# sensorboard_spectrometer_rev0.net
KiCad netlist of a schematic drawn in EAGLE
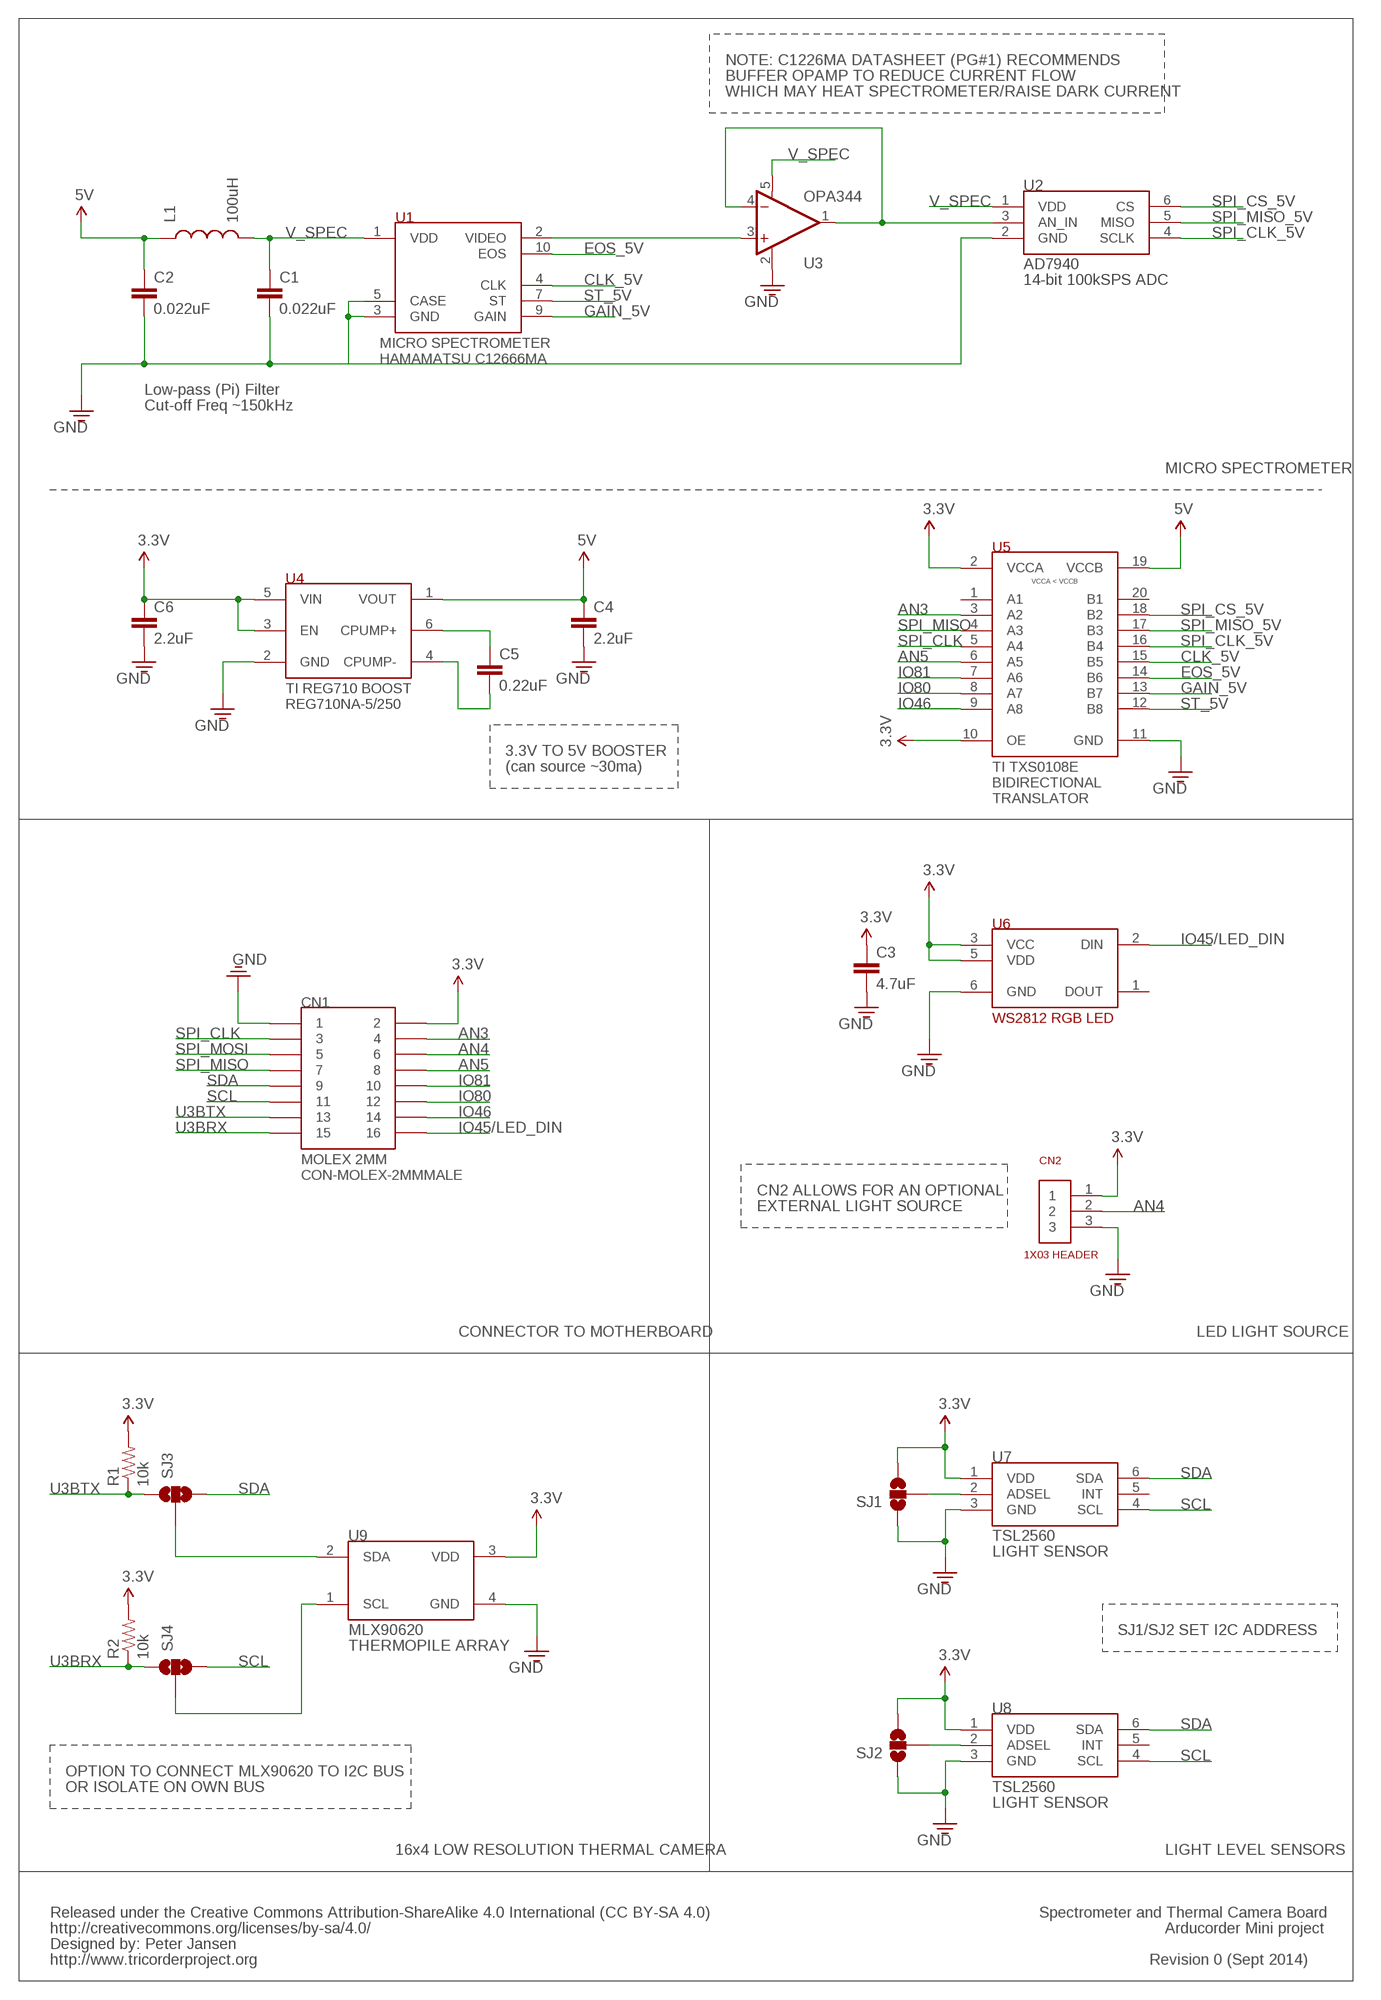
[diagram p0: schematic, sheet 1]

(export (version "E")
  (design (tool "Eeschema 10.0.6"))
  (components
    (comp (ref "C1")
      (value "0.022uF")
      (footprint "eagle-import:0603")
      (libsource (lib "eagle-import") (part "notes_mark5_CAP0603"))
    )
    (comp (ref "C2")
      (value "0.022uF")
      (footprint "eagle-import:0603")
      (libsource (lib "eagle-import") (part "notes_mark5_CAP0603"))
    )
    (comp (ref "C3")
      (value "4.7uF")
      (footprint "eagle-import:0603")
      (libsource (lib "eagle-import") (part "notes_mark5a_CAP0603"))
    )
    (comp (ref "C4")
      (value "2.2uF")
      (footprint "eagle-import:0603")
      (libsource (lib "eagle-import") (part "CAP0603"))
    )
    (comp (ref "C5")
      (value "0.22uF")
      (footprint "eagle-import:0603")
      (libsource (lib "eagle-import") (part "CAP0603"))
    )
    (comp (ref "C6")
      (value "2.2uF")
      (footprint "eagle-import:0603")
      (libsource (lib "eagle-import") (part "CAP0603"))
    )
    (comp (ref "CN1")
      (value "CON-MOLEX-2MMMALE")
      (footprint "eagle-import:MOLEX-0877591650")
      (libsource (lib "eagle-import") (part "CON-MOLEX-2MMMALE"))
    )
    (comp (ref "CN2")
      (value "1X03")
      (footprint "eagle-import:1X03")
      (libsource (lib "eagle-import") (part "1X03"))
    )
    (comp (ref "L1")
      (value "100uH")
      (footprint "eagle-import:0805")
      (libsource (lib "eagle-import") (part "INDUCTOR0805"))
    )
    (comp (ref "R1")
      (value "10k")
      (footprint "eagle-import:0603")
      (libsource (lib "eagle-import") (part "RESISTOR0603"))
    )
    (comp (ref "R2")
      (value "10k")
      (footprint "eagle-import:0603")
      (libsource (lib "eagle-import") (part "RESISTOR0603"))
    )
    (comp (ref "SJ1")
      (value "SOLDERJUMPER_2WAYPASTE1&2")
      (footprint "eagle-import:SJ_3_PASTE1&2")
      (libsource (lib "eagle-import") (part "SOLDERJUMPER_2WAYPASTE1&2"))
    )
    (comp (ref "SJ2")
      (value "SOLDERJUMPER_2WAYPASTE2&3")
      (footprint "eagle-import:SJ_3_PASTE2&3")
      (libsource (lib "eagle-import") (part "SOLDERJUMPER_2WAYPASTE2&3"))
    )
    (comp (ref "SJ3")
      (value "SOLDERJUMPER_2WAYPASTE1&2")
      (footprint "eagle-import:SJ_3_PASTE1&2")
      (libsource (lib "eagle-import") (part "SOLDERJUMPER_2WAYPASTE1&2"))
    )
    (comp (ref "SJ4")
      (value "SOLDERJUMPER_2WAYPASTE1&2")
      (footprint "eagle-import:SJ_3_PASTE1&2")
      (libsource (lib "eagle-import") (part "SOLDERJUMPER_2WAYPASTE1&2"))
    )
    (comp (ref "U1")
      (value "MICROSPEC-C12666MA")
      (footprint "eagle-import:C12666MA")
      (libsource (lib "eagle-import") (part "MICROSPEC-C12666MA"))
    )
    (comp (ref "U2")
      (value "AD7940")
      (footprint "eagle-import:SOT-23-6L")
      (libsource (lib "eagle-import") (part "AD7940"))
    )
    (comp (ref "U3")
      (value "OPA344")
      (footprint "eagle-import:SOT23-5")
      (libsource (lib "eagle-import") (part "OPA344"))
    )
    (comp (ref "U4")
      (value "REG710NA-5/250")
      (footprint "eagle-import:SOT-23-6L")
      (libsource (lib "eagle-import") (part "TI-REG710"))
    )
    (comp (ref "U5")
      (value "TRANSLATOR-TXS0108E")
      (footprint "eagle-import:TSSOP-20")
      (libsource (lib "eagle-import") (part "TRANSLATOR-TXS0108E"))
    )
    (comp (ref "U6")
      (value "WS2812_NEOPIXEL")
      (footprint "eagle-import:WS2812")
      (libsource (lib "eagle-import") (part "WS2812_NEOPIXEL"))
    )
    (comp (ref "U7")
      (value "TSL2561")
      (footprint "eagle-import:TMB-6")
      (libsource (lib "eagle-import") (part "TSL2561"))
    )
    (comp (ref "U8")
      (value "TSL2561")
      (footprint "eagle-import:TMB-6")
      (libsource (lib "eagle-import") (part "TSL2561"))
    )
    (comp (ref "U9")
      (value "MLX90620")
      (footprint "eagle-import:MLX90620")
      (libsource (lib "eagle-import") (part "MLX90620"))
    )
  )
  (nets
    (net (code "1") (name "/AN3") (class "Default")
      (node (ref "CN1") (pin "4") (pinfunction "4_4") (pintype "bidirectional"))
      (node (ref "U5") (pin "3") (pinfunction "A2_3") (pintype "bidirectional"))
    )
    (net (code "2") (name "/AN4") (class "Default")
      (node (ref "CN1") (pin "6") (pinfunction "6_6") (pintype "bidirectional"))
      (node (ref "CN2") (pin "2") (pinfunction "2_2") (pintype "bidirectional"))
    )
    (net (code "3") (name "/AN5") (class "Default")
      (node (ref "CN1") (pin "8") (pinfunction "8_8") (pintype "bidirectional"))
      (node (ref "U5") (pin "6") (pinfunction "A5_6") (pintype "bidirectional"))
    )
    (net (code "4") (name "/CLK_5V") (class "Default")
      (node (ref "U1") (pin "4") (pinfunction "CLK_4") (pintype "bidirectional"))
      (node (ref "U5") (pin "15") (pinfunction "B5_15") (pintype "bidirectional"))
    )
    (net (code "5") (name "/EOS_5V") (class "Default")
      (node (ref "U1") (pin "10") (pinfunction "EOS_10") (pintype "bidirectional"))
      (node (ref "U5") (pin "14") (pinfunction "B6_14") (pintype "bidirectional"))
    )
    (net (code "6") (name "/GAIN_5V") (class "Default")
      (node (ref "U1") (pin "9") (pinfunction "GAIN_9") (pintype "bidirectional"))
      (node (ref "U5") (pin "13") (pinfunction "B7_13") (pintype "bidirectional"))
    )
    (net (code "7") (name "/IO45{slash}LED_DIN") (class "Default")
      (node (ref "CN1") (pin "16") (pinfunction "16_16") (pintype "bidirectional"))
      (node (ref "U6") (pin "2") (pinfunction "DIN_2") (pintype "bidirectional"))
    )
    (net (code "8") (name "/IO46") (class "Default")
      (node (ref "CN1") (pin "14") (pinfunction "14_14") (pintype "bidirectional"))
      (node (ref "U5") (pin "9") (pinfunction "A8_9") (pintype "bidirectional"))
    )
    (net (code "9") (name "/IO80") (class "Default")
      (node (ref "CN1") (pin "12") (pinfunction "12_12") (pintype "bidirectional"))
      (node (ref "U5") (pin "8") (pinfunction "A7_8") (pintype "bidirectional"))
    )
    (net (code "10") (name "/IO81") (class "Default")
      (node (ref "CN1") (pin "10") (pinfunction "10_10") (pintype "bidirectional"))
      (node (ref "U5") (pin "7") (pinfunction "A6_7") (pintype "bidirectional"))
    )
    (net (code "11") (name "/SCL") (class "Default")
      (node (ref "CN1") (pin "11") (pinfunction "11_11") (pintype "bidirectional"))
      (node (ref "SJ4") (pin "3") (pinfunction "3_3") (pintype "passive"))
      (node (ref "U7") (pin "4") (pinfunction "SCL_4") (pintype "bidirectional"))
      (node (ref "U8") (pin "4") (pinfunction "SCL_4") (pintype "bidirectional"))
    )
    (net (code "12") (name "/SDA") (class "Default")
      (node (ref "CN1") (pin "9") (pinfunction "9_9") (pintype "bidirectional"))
      (node (ref "SJ3") (pin "3") (pinfunction "3_3") (pintype "passive"))
      (node (ref "U7") (pin "6") (pinfunction "SDA_6") (pintype "bidirectional"))
      (node (ref "U8") (pin "6") (pinfunction "SDA_6") (pintype "bidirectional"))
    )
    (net (code "13") (name "/SPI_CLK") (class "Default")
      (node (ref "CN1") (pin "3") (pinfunction "3_3") (pintype "bidirectional"))
      (node (ref "U5") (pin "5") (pinfunction "A4_5") (pintype "bidirectional"))
    )
    (net (code "14") (name "/SPI_CLK_5V") (class "Default")
      (node (ref "U2") (pin "4") (pinfunction "SCLK_4") (pintype "bidirectional"))
      (node (ref "U5") (pin "16") (pinfunction "B4_16") (pintype "bidirectional"))
    )
    (net (code "15") (name "/SPI_CS_5V") (class "Default")
      (node (ref "U2") (pin "6") (pinfunction "CS_6") (pintype "bidirectional"))
      (node (ref "U5") (pin "18") (pinfunction "B2_18") (pintype "bidirectional"))
    )
    (net (code "16") (name "/SPI_MISO") (class "Default")
      (node (ref "CN1") (pin "7") (pinfunction "7_7") (pintype "bidirectional"))
      (node (ref "U5") (pin "4") (pinfunction "A3_4") (pintype "bidirectional"))
    )
    (net (code "17") (name "/SPI_MISO_5V") (class "Default")
      (node (ref "U2") (pin "5") (pinfunction "MISO_5") (pintype "bidirectional"))
      (node (ref "U5") (pin "17") (pinfunction "B3_17") (pintype "bidirectional"))
    )
    (net (code "18") (name "/SPI_MOSI") (class "Default")
      (node (ref "CN1") (pin "5") (pinfunction "5_5") (pintype "bidirectional"))
    )
    (net (code "19") (name "/ST_5V") (class "Default")
      (node (ref "U1") (pin "7") (pinfunction "ST_7") (pintype "bidirectional"))
      (node (ref "U5") (pin "12") (pinfunction "B8_12") (pintype "bidirectional"))
    )
    (net (code "20") (name "/U3BRX") (class "Default")
      (node (ref "CN1") (pin "15") (pinfunction "15_15") (pintype "bidirectional"))
      (node (ref "R2") (pin "1") (pinfunction "1_1") (pintype "passive"))
      (node (ref "SJ4") (pin "1") (pinfunction "1_1") (pintype "passive"))
    )
    (net (code "21") (name "/U3BTX") (class "Default")
      (node (ref "CN1") (pin "13") (pinfunction "13_13") (pintype "bidirectional"))
      (node (ref "R1") (pin "1") (pinfunction "1_1") (pintype "passive"))
      (node (ref "SJ3") (pin "1") (pinfunction "1_1") (pintype "passive"))
    )
    (net (code "22") (name "/V_SPEC") (class "Default")
      (node (ref "C1") (pin "1") (pinfunction "1_1") (pintype "passive"))
      (node (ref "L1") (pin "2") (pinfunction "2_2") (pintype "passive"))
      (node (ref "U1") (pin "1") (pinfunction "VDD_1") (pintype "bidirectional"))
      (node (ref "U2") (pin "1") (pinfunction "VDD_1") (pintype "bidirectional"))
      (node (ref "U3") (pin "5") (pinfunction "V+_5") (pintype "power_in"))
    )
    (net (code "23") (name "3.3V") (class "Default")
      (node (ref "C3") (pin "1") (pinfunction "1_1") (pintype "passive"))
      (node (ref "C6") (pin "1") (pinfunction "1_1") (pintype "passive"))
      (node (ref "CN1") (pin "2") (pinfunction "2_2") (pintype "bidirectional"))
      (node (ref "CN2") (pin "1") (pinfunction "1_1") (pintype "bidirectional"))
      (node (ref "R1") (pin "2") (pinfunction "2_2") (pintype "passive"))
      (node (ref "R2") (pin "2") (pinfunction "2_2") (pintype "passive"))
      (node (ref "SJ1") (pin "3") (pinfunction "3_3") (pintype "passive"))
      (node (ref "SJ2") (pin "3") (pinfunction "3_3") (pintype "passive"))
      (node (ref "U4") (pin "3") (pinfunction "EN_3") (pintype "bidirectional"))
      (node (ref "U4") (pin "5") (pinfunction "VIN_5") (pintype "bidirectional"))
      (node (ref "U5") (pin "10") (pinfunction "OE_10") (pintype "bidirectional"))
      (node (ref "U5") (pin "2") (pinfunction "VCCA_2") (pintype "bidirectional"))
      (node (ref "U6") (pin "3") (pinfunction "VCC_3") (pintype "bidirectional"))
      (node (ref "U6") (pin "5") (pinfunction "VDD_5") (pintype "bidirectional"))
      (node (ref "U7") (pin "1") (pinfunction "VDD_1") (pintype "bidirectional"))
      (node (ref "U8") (pin "1") (pinfunction "VDD_1") (pintype "bidirectional"))
      (node (ref "U9") (pin "3") (pinfunction "VDD_3") (pintype "bidirectional"))
    )
    (net (code "24") (name "5V") (class "Default")
      (node (ref "C2") (pin "1") (pinfunction "1_1") (pintype "passive"))
      (node (ref "C4") (pin "1") (pinfunction "1_1") (pintype "passive"))
      (node (ref "L1") (pin "1") (pinfunction "1_1") (pintype "passive"))
      (node (ref "U4") (pin "1") (pinfunction "VOUT_1") (pintype "bidirectional"))
      (node (ref "U5") (pin "19") (pinfunction "VCCB_19") (pintype "bidirectional"))
    )
    (net (code "25") (name "GND") (class "Default")
      (node (ref "C1") (pin "2") (pinfunction "2_2") (pintype "passive"))
      (node (ref "C2") (pin "2") (pinfunction "2_2") (pintype "passive"))
      (node (ref "C3") (pin "2") (pinfunction "2_2") (pintype "passive"))
      (node (ref "C4") (pin "2") (pinfunction "2_2") (pintype "passive"))
      (node (ref "C6") (pin "2") (pinfunction "2_2") (pintype "passive"))
      (node (ref "CN1") (pin "1") (pinfunction "1_1") (pintype "bidirectional"))
      (node (ref "CN2") (pin "3") (pinfunction "3_3") (pintype "bidirectional"))
      (node (ref "SJ1") (pin "1") (pinfunction "1_1") (pintype "passive"))
      (node (ref "SJ2") (pin "1") (pinfunction "1_1") (pintype "passive"))
      (node (ref "U1") (pin "3") (pinfunction "GND_3") (pintype "bidirectional"))
      (node (ref "U1") (pin "5") (pinfunction "CASE_5") (pintype "bidirectional"))
      (node (ref "U2") (pin "2") (pinfunction "GND_2") (pintype "bidirectional"))
      (node (ref "U3") (pin "2") (pinfunction "V-_2") (pintype "power_in"))
      (node (ref "U4") (pin "2") (pinfunction "GND_2") (pintype "bidirectional"))
      (node (ref "U5") (pin "11") (pinfunction "GND_11") (pintype "bidirectional"))
      (node (ref "U6") (pin "6") (pinfunction "GND_6") (pintype "bidirectional"))
      (node (ref "U7") (pin "3") (pinfunction "GND_3") (pintype "bidirectional"))
      (node (ref "U8") (pin "3") (pinfunction "GND_3") (pintype "bidirectional"))
      (node (ref "U9") (pin "4") (pinfunction "GND_4") (pintype "bidirectional"))
    )
    (net (code "26") (name "Net-(U1-VIDEO)") (class "Default")
      (node (ref "U1") (pin "2") (pinfunction "VIDEO_2") (pintype "bidirectional"))
      (node (ref "U3") (pin "3") (pinfunction "+IN_3") (pintype "input"))
    )
    (net (code "27") (name "Net-(U2-AN_IN)") (class "Default")
      (node (ref "U2") (pin "3") (pinfunction "AN_IN_3") (pintype "bidirectional"))
      (node (ref "U3") (pin "1") (pinfunction "OUT_1") (pintype "output"))
      (node (ref "U3") (pin "4") (pinfunction "-IN_4") (pintype "input"))
    )
    (net (code "28") (name "Net-(U4-CPUMP+)") (class "Default")
      (node (ref "C5") (pin "1") (pinfunction "1_1") (pintype "passive"))
      (node (ref "U4") (pin "6") (pinfunction "CPUMP+_6") (pintype "bidirectional"))
    )
    (net (code "29") (name "Net-(U4-CPUMP-)") (class "Default")
      (node (ref "C5") (pin "2") (pinfunction "2_2") (pintype "passive"))
      (node (ref "U4") (pin "4") (pinfunction "CPUMP-_4") (pintype "bidirectional"))
    )
    (net (code "30") (name "Net-(U7-ADSEL)") (class "Default")
      (node (ref "SJ1") (pin "2") (pinfunction "2_2") (pintype "passive"))
      (node (ref "U7") (pin "2") (pinfunction "ADSEL_2") (pintype "bidirectional"))
    )
    (net (code "31") (name "Net-(U8-ADSEL)") (class "Default")
      (node (ref "SJ2") (pin "2") (pinfunction "2_2") (pintype "passive"))
      (node (ref "U8") (pin "2") (pinfunction "ADSEL_2") (pintype "bidirectional"))
    )
    (net (code "32") (name "Net-(U9-SCL)") (class "Default")
      (node (ref "SJ4") (pin "2") (pinfunction "2_2") (pintype "passive"))
      (node (ref "U9") (pin "1") (pinfunction "SCL_1") (pintype "bidirectional"))
    )
    (net (code "33") (name "Net-(U9-SDA)") (class "Default")
      (node (ref "SJ3") (pin "2") (pinfunction "2_2") (pintype "passive"))
      (node (ref "U9") (pin "2") (pinfunction "SDA_2") (pintype "bidirectional"))
    )
    (net (code "34") (name "unconnected-(U5-A1-Pad1)") (class "Default")
      (node (ref "U5") (pin "1") (pinfunction "A1_1") (pintype "bidirectional"))
    )
    (net (code "35") (name "unconnected-(U5-B1-Pad20)") (class "Default")
      (node (ref "U5") (pin "20") (pinfunction "B1_20") (pintype "bidirectional"))
    )
    (net (code "36") (name "unconnected-(U6-DOUT-Pad1)") (class "Default")
      (node (ref "U6") (pin "1") (pinfunction "DOUT_1") (pintype "bidirectional"))
    )
    (net (code "37") (name "unconnected-(U7-INT-Pad5)") (class "Default")
      (node (ref "U7") (pin "5") (pinfunction "INT_5") (pintype "bidirectional"))
    )
    (net (code "38") (name "unconnected-(U8-INT-Pad5)") (class "Default")
      (node (ref "U8") (pin "5") (pinfunction "INT_5") (pintype "bidirectional"))
    )
  )
)
